# transceiver.net
KiCad netlist of a schematic drawn in Altium Designer
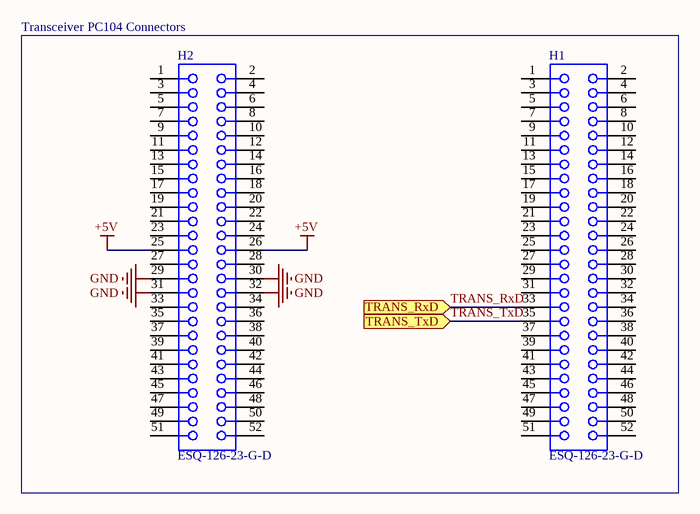
[diagram p0: transceiver.SchDoc]

(export (version "E")
  (design (tool "Eeschema 10.0.6"))
  (components
    (comp (ref "H1")
      (value "ESQ-126-23-G-D")
      (footprint "heron-general:SSW-126-01-G-D")
      (fields (field (name "MANUFACTURER") "Samtec"))
      (libsource (lib "CONNs") (part "ESQ-126-23-G-D"))
    )
    (comp (ref "H2")
      (value "ESQ-126-23-G-D")
      (footprint "SSW-126-01-G-D")
      (fields (field (name "MANUFACTURER") "Samtec"))
      (libsource (lib "heron-general") (part "ESQ-126-23-G-D"))
    )
  )
  (nets
    (net (code "1") (name "+5V") (class "Default")
      (node (ref "H2") (pin "25") (pinfunction "25_25") (pintype "passive"))
      (node (ref "H2") (pin "26") (pinfunction "26_26") (pintype "passive"))
    )
    (net (code "2") (name "/TRANS_RxD") (class "Default")
      (node (ref "H1") (pin "33") (pinfunction "33_33") (pintype "passive"))
    )
    (net (code "3") (name "/TRANS_TxD") (class "Default")
      (node (ref "H1") (pin "35") (pinfunction "35_35") (pintype "passive"))
    )
    (net (code "4") (name "GND") (class "Default")
      (node (ref "H2") (pin "29") (pinfunction "29_29") (pintype "passive"))
      (node (ref "H2") (pin "30") (pinfunction "30_30") (pintype "passive"))
      (node (ref "H2") (pin "31") (pinfunction "31_31") (pintype "passive"))
      (node (ref "H2") (pin "32") (pinfunction "32_32") (pintype "passive"))
    )
    (net (code "5") (name "unconnected-(H1-Pad1)") (class "Default")
      (node (ref "H1") (pin "1") (pinfunction "1_1") (pintype "passive"))
    )
    (net (code "6") (name "unconnected-(H1-Pad2)") (class "Default")
      (node (ref "H1") (pin "2") (pinfunction "2_2") (pintype "passive"))
    )
    (net (code "7") (name "unconnected-(H1-Pad3)") (class "Default")
      (node (ref "H1") (pin "3") (pinfunction "3_3") (pintype "passive"))
    )
    (net (code "8") (name "unconnected-(H1-Pad4)") (class "Default")
      (node (ref "H1") (pin "4") (pinfunction "4_4") (pintype "passive"))
    )
    (net (code "9") (name "unconnected-(H1-Pad5)") (class "Default")
      (node (ref "H1") (pin "5") (pinfunction "5_5") (pintype "passive"))
    )
    (net (code "10") (name "unconnected-(H1-Pad6)") (class "Default")
      (node (ref "H1") (pin "6") (pinfunction "6_6") (pintype "passive"))
    )
    (net (code "11") (name "unconnected-(H1-Pad7)") (class "Default")
      (node (ref "H1") (pin "7") (pinfunction "7_7") (pintype "passive"))
    )
    (net (code "12") (name "unconnected-(H1-Pad8)") (class "Default")
      (node (ref "H1") (pin "8") (pinfunction "8_8") (pintype "passive"))
    )
    (net (code "13") (name "unconnected-(H1-Pad9)") (class "Default")
      (node (ref "H1") (pin "9") (pinfunction "9_9") (pintype "passive"))
    )
    (net (code "14") (name "unconnected-(H1-Pad10)") (class "Default")
      (node (ref "H1") (pin "10") (pinfunction "10_10") (pintype "passive"))
    )
    (net (code "15") (name "unconnected-(H1-Pad11)") (class "Default")
      (node (ref "H1") (pin "11") (pinfunction "11_11") (pintype "passive"))
    )
    (net (code "16") (name "unconnected-(H1-Pad12)") (class "Default")
      (node (ref "H1") (pin "12") (pinfunction "12_12") (pintype "passive"))
    )
    (net (code "17") (name "unconnected-(H1-Pad13)") (class "Default")
      (node (ref "H1") (pin "13") (pinfunction "13_13") (pintype "passive"))
    )
    (net (code "18") (name "unconnected-(H1-Pad14)") (class "Default")
      (node (ref "H1") (pin "14") (pinfunction "14_14") (pintype "passive"))
    )
    (net (code "19") (name "unconnected-(H1-Pad15)") (class "Default")
      (node (ref "H1") (pin "15") (pinfunction "15_15") (pintype "passive"))
    )
    (net (code "20") (name "unconnected-(H1-Pad16)") (class "Default")
      (node (ref "H1") (pin "16") (pinfunction "16_16") (pintype "passive"))
    )
    (net (code "21") (name "unconnected-(H1-Pad17)") (class "Default")
      (node (ref "H1") (pin "17") (pinfunction "17_17") (pintype "passive"))
    )
    (net (code "22") (name "unconnected-(H1-Pad18)") (class "Default")
      (node (ref "H1") (pin "18") (pinfunction "18_18") (pintype "passive"))
    )
    (net (code "23") (name "unconnected-(H1-Pad19)") (class "Default")
      (node (ref "H1") (pin "19") (pinfunction "19_19") (pintype "passive"))
    )
    (net (code "24") (name "unconnected-(H1-Pad20)") (class "Default")
      (node (ref "H1") (pin "20") (pinfunction "20_20") (pintype "passive"))
    )
    (net (code "25") (name "unconnected-(H1-Pad21)") (class "Default")
      (node (ref "H1") (pin "21") (pinfunction "21_21") (pintype "passive"))
    )
    (net (code "26") (name "unconnected-(H1-Pad22)") (class "Default")
      (node (ref "H1") (pin "22") (pinfunction "22_22") (pintype "passive"))
    )
    (net (code "27") (name "unconnected-(H1-Pad23)") (class "Default")
      (node (ref "H1") (pin "23") (pinfunction "23_23") (pintype "passive"))
    )
    (net (code "28") (name "unconnected-(H1-Pad24)") (class "Default")
      (node (ref "H1") (pin "24") (pinfunction "24_24") (pintype "passive"))
    )
    (net (code "29") (name "unconnected-(H1-Pad25)") (class "Default")
      (node (ref "H1") (pin "25") (pinfunction "25_25") (pintype "passive"))
    )
    (net (code "30") (name "unconnected-(H1-Pad26)") (class "Default")
      (node (ref "H1") (pin "26") (pinfunction "26_26") (pintype "passive"))
    )
    (net (code "31") (name "unconnected-(H1-Pad27)") (class "Default")
      (node (ref "H1") (pin "27") (pinfunction "27_27") (pintype "passive"))
    )
    (net (code "32") (name "unconnected-(H1-Pad28)") (class "Default")
      (node (ref "H1") (pin "28") (pinfunction "28_28") (pintype "passive"))
    )
    (net (code "33") (name "unconnected-(H1-Pad29)") (class "Default")
      (node (ref "H1") (pin "29") (pinfunction "29_29") (pintype "passive"))
    )
    (net (code "34") (name "unconnected-(H1-Pad30)") (class "Default")
      (node (ref "H1") (pin "30") (pinfunction "30_30") (pintype "passive"))
    )
    (net (code "35") (name "unconnected-(H1-Pad31)") (class "Default")
      (node (ref "H1") (pin "31") (pinfunction "31_31") (pintype "passive"))
    )
    (net (code "36") (name "unconnected-(H1-Pad32)") (class "Default")
      (node (ref "H1") (pin "32") (pinfunction "32_32") (pintype "passive"))
    )
    (net (code "37") (name "unconnected-(H1-Pad34)") (class "Default")
      (node (ref "H1") (pin "34") (pinfunction "34_34") (pintype "passive"))
    )
    (net (code "38") (name "unconnected-(H1-Pad36)") (class "Default")
      (node (ref "H1") (pin "36") (pinfunction "36_36") (pintype "passive"))
    )
    (net (code "39") (name "unconnected-(H1-Pad37)") (class "Default")
      (node (ref "H1") (pin "37") (pinfunction "37_37") (pintype "passive"))
    )
    (net (code "40") (name "unconnected-(H1-Pad38)") (class "Default")
      (node (ref "H1") (pin "38") (pinfunction "38_38") (pintype "passive"))
    )
    (net (code "41") (name "unconnected-(H1-Pad39)") (class "Default")
      (node (ref "H1") (pin "39") (pinfunction "39_39") (pintype "passive"))
    )
    (net (code "42") (name "unconnected-(H1-Pad40)") (class "Default")
      (node (ref "H1") (pin "40") (pinfunction "40_40") (pintype "passive"))
    )
    (net (code "43") (name "unconnected-(H1-Pad41)") (class "Default")
      (node (ref "H1") (pin "41") (pinfunction "41_41") (pintype "passive"))
    )
    (net (code "44") (name "unconnected-(H1-Pad42)") (class "Default")
      (node (ref "H1") (pin "42") (pinfunction "42_42") (pintype "passive"))
    )
    (net (code "45") (name "unconnected-(H1-Pad43)") (class "Default")
      (node (ref "H1") (pin "43") (pinfunction "43_43") (pintype "passive"))
    )
    (net (code "46") (name "unconnected-(H1-Pad44)") (class "Default")
      (node (ref "H1") (pin "44") (pinfunction "44_44") (pintype "passive"))
    )
    (net (code "47") (name "unconnected-(H1-Pad45)") (class "Default")
      (node (ref "H1") (pin "45") (pinfunction "45_45") (pintype "passive"))
    )
    (net (code "48") (name "unconnected-(H1-Pad46)") (class "Default")
      (node (ref "H1") (pin "46") (pinfunction "46_46") (pintype "passive"))
    )
    (net (code "49") (name "unconnected-(H1-Pad47)") (class "Default")
      (node (ref "H1") (pin "47") (pinfunction "47_47") (pintype "passive"))
    )
    (net (code "50") (name "unconnected-(H1-Pad48)") (class "Default")
      (node (ref "H1") (pin "48") (pinfunction "48_48") (pintype "passive"))
    )
    (net (code "51") (name "unconnected-(H1-Pad49)") (class "Default")
      (node (ref "H1") (pin "49") (pinfunction "49_49") (pintype "passive"))
    )
    (net (code "52") (name "unconnected-(H1-Pad50)") (class "Default")
      (node (ref "H1") (pin "50") (pinfunction "50_50") (pintype "passive"))
    )
    (net (code "53") (name "unconnected-(H1-Pad51)") (class "Default")
      (node (ref "H1") (pin "51") (pinfunction "51_51") (pintype "passive"))
    )
    (net (code "54") (name "unconnected-(H1-Pad52)") (class "Default")
      (node (ref "H1") (pin "52") (pinfunction "52_52") (pintype "passive"))
    )
    (net (code "55") (name "unconnected-(H2-Pad1)") (class "Default")
      (node (ref "H2") (pin "1") (pinfunction "1_1") (pintype "passive"))
    )
    (net (code "56") (name "unconnected-(H2-Pad2)") (class "Default")
      (node (ref "H2") (pin "2") (pinfunction "2_2") (pintype "passive"))
    )
    (net (code "57") (name "unconnected-(H2-Pad3)") (class "Default")
      (node (ref "H2") (pin "3") (pinfunction "3_3") (pintype "passive"))
    )
    (net (code "58") (name "unconnected-(H2-Pad4)") (class "Default")
      (node (ref "H2") (pin "4") (pinfunction "4_4") (pintype "passive"))
    )
    (net (code "59") (name "unconnected-(H2-Pad5)") (class "Default")
      (node (ref "H2") (pin "5") (pinfunction "5_5") (pintype "passive"))
    )
    (net (code "60") (name "unconnected-(H2-Pad6)") (class "Default")
      (node (ref "H2") (pin "6") (pinfunction "6_6") (pintype "passive"))
    )
    (net (code "61") (name "unconnected-(H2-Pad7)") (class "Default")
      (node (ref "H2") (pin "7") (pinfunction "7_7") (pintype "passive"))
    )
    (net (code "62") (name "unconnected-(H2-Pad8)") (class "Default")
      (node (ref "H2") (pin "8") (pinfunction "8_8") (pintype "passive"))
    )
    (net (code "63") (name "unconnected-(H2-Pad9)") (class "Default")
      (node (ref "H2") (pin "9") (pinfunction "9_9") (pintype "passive"))
    )
    (net (code "64") (name "unconnected-(H2-Pad10)") (class "Default")
      (node (ref "H2") (pin "10") (pinfunction "10_10") (pintype "passive"))
    )
    (net (code "65") (name "unconnected-(H2-Pad11)") (class "Default")
      (node (ref "H2") (pin "11") (pinfunction "11_11") (pintype "passive"))
    )
    (net (code "66") (name "unconnected-(H2-Pad12)") (class "Default")
      (node (ref "H2") (pin "12") (pinfunction "12_12") (pintype "passive"))
    )
    (net (code "67") (name "unconnected-(H2-Pad13)") (class "Default")
      (node (ref "H2") (pin "13") (pinfunction "13_13") (pintype "passive"))
    )
    (net (code "68") (name "unconnected-(H2-Pad14)") (class "Default")
      (node (ref "H2") (pin "14") (pinfunction "14_14") (pintype "passive"))
    )
    (net (code "69") (name "unconnected-(H2-Pad15)") (class "Default")
      (node (ref "H2") (pin "15") (pinfunction "15_15") (pintype "passive"))
    )
    (net (code "70") (name "unconnected-(H2-Pad16)") (class "Default")
      (node (ref "H2") (pin "16") (pinfunction "16_16") (pintype "passive"))
    )
    (net (code "71") (name "unconnected-(H2-Pad17)") (class "Default")
      (node (ref "H2") (pin "17") (pinfunction "17_17") (pintype "passive"))
    )
    (net (code "72") (name "unconnected-(H2-Pad18)") (class "Default")
      (node (ref "H2") (pin "18") (pinfunction "18_18") (pintype "passive"))
    )
    (net (code "73") (name "unconnected-(H2-Pad19)") (class "Default")
      (node (ref "H2") (pin "19") (pinfunction "19_19") (pintype "passive"))
    )
    (net (code "74") (name "unconnected-(H2-Pad20)") (class "Default")
      (node (ref "H2") (pin "20") (pinfunction "20_20") (pintype "passive"))
    )
    (net (code "75") (name "unconnected-(H2-Pad21)") (class "Default")
      (node (ref "H2") (pin "21") (pinfunction "21_21") (pintype "passive"))
    )
    (net (code "76") (name "unconnected-(H2-Pad22)") (class "Default")
      (node (ref "H2") (pin "22") (pinfunction "22_22") (pintype "passive"))
    )
    (net (code "77") (name "unconnected-(H2-Pad23)") (class "Default")
      (node (ref "H2") (pin "23") (pinfunction "23_23") (pintype "passive"))
    )
    (net (code "78") (name "unconnected-(H2-Pad24)") (class "Default")
      (node (ref "H2") (pin "24") (pinfunction "24_24") (pintype "passive"))
    )
    (net (code "79") (name "unconnected-(H2-Pad27)") (class "Default")
      (node (ref "H2") (pin "27") (pinfunction "27_27") (pintype "passive"))
    )
    (net (code "80") (name "unconnected-(H2-Pad28)") (class "Default")
      (node (ref "H2") (pin "28") (pinfunction "28_28") (pintype "passive"))
    )
    (net (code "81") (name "unconnected-(H2-Pad33)") (class "Default")
      (node (ref "H2") (pin "33") (pinfunction "33_33") (pintype "passive"))
    )
    (net (code "82") (name "unconnected-(H2-Pad34)") (class "Default")
      (node (ref "H2") (pin "34") (pinfunction "34_34") (pintype "passive"))
    )
    (net (code "83") (name "unconnected-(H2-Pad35)") (class "Default")
      (node (ref "H2") (pin "35") (pinfunction "35_35") (pintype "passive"))
    )
    (net (code "84") (name "unconnected-(H2-Pad36)") (class "Default")
      (node (ref "H2") (pin "36") (pinfunction "36_36") (pintype "passive"))
    )
    (net (code "85") (name "unconnected-(H2-Pad37)") (class "Default")
      (node (ref "H2") (pin "37") (pinfunction "37_37") (pintype "passive"))
    )
    (net (code "86") (name "unconnected-(H2-Pad38)") (class "Default")
      (node (ref "H2") (pin "38") (pinfunction "38_38") (pintype "passive"))
    )
    (net (code "87") (name "unconnected-(H2-Pad39)") (class "Default")
      (node (ref "H2") (pin "39") (pinfunction "39_39") (pintype "passive"))
    )
    (net (code "88") (name "unconnected-(H2-Pad40)") (class "Default")
      (node (ref "H2") (pin "40") (pinfunction "40_40") (pintype "passive"))
    )
    (net (code "89") (name "unconnected-(H2-Pad41)") (class "Default")
      (node (ref "H2") (pin "41") (pinfunction "41_41") (pintype "passive"))
    )
    (net (code "90") (name "unconnected-(H2-Pad42)") (class "Default")
      (node (ref "H2") (pin "42") (pinfunction "42_42") (pintype "passive"))
    )
    (net (code "91") (name "unconnected-(H2-Pad43)") (class "Default")
      (node (ref "H2") (pin "43") (pinfunction "43_43") (pintype "passive"))
    )
    (net (code "92") (name "unconnected-(H2-Pad44)") (class "Default")
      (node (ref "H2") (pin "44") (pinfunction "44_44") (pintype "passive"))
    )
    (net (code "93") (name "unconnected-(H2-Pad45)") (class "Default")
      (node (ref "H2") (pin "45") (pinfunction "45_45") (pintype "passive"))
    )
    (net (code "94") (name "unconnected-(H2-Pad46)") (class "Default")
      (node (ref "H2") (pin "46") (pinfunction "46_46") (pintype "passive"))
    )
    (net (code "95") (name "unconnected-(H2-Pad47)") (class "Default")
      (node (ref "H2") (pin "47") (pinfunction "47_47") (pintype "passive"))
    )
    (net (code "96") (name "unconnected-(H2-Pad48)") (class "Default")
      (node (ref "H2") (pin "48") (pinfunction "48_48") (pintype "passive"))
    )
    (net (code "97") (name "unconnected-(H2-Pad49)") (class "Default")
      (node (ref "H2") (pin "49") (pinfunction "49_49") (pintype "passive"))
    )
    (net (code "98") (name "unconnected-(H2-Pad50)") (class "Default")
      (node (ref "H2") (pin "50") (pinfunction "50_50") (pintype "passive"))
    )
    (net (code "99") (name "unconnected-(H2-Pad51)") (class "Default")
      (node (ref "H2") (pin "51") (pinfunction "51_51") (pintype "passive"))
    )
    (net (code "100") (name "unconnected-(H2-Pad52)") (class "Default")
      (node (ref "H2") (pin "52") (pinfunction "52_52") (pintype "passive"))
    )
  )
)
